# envelope_detection.net
KiCad netlist of a schematic drawn in EAGLE
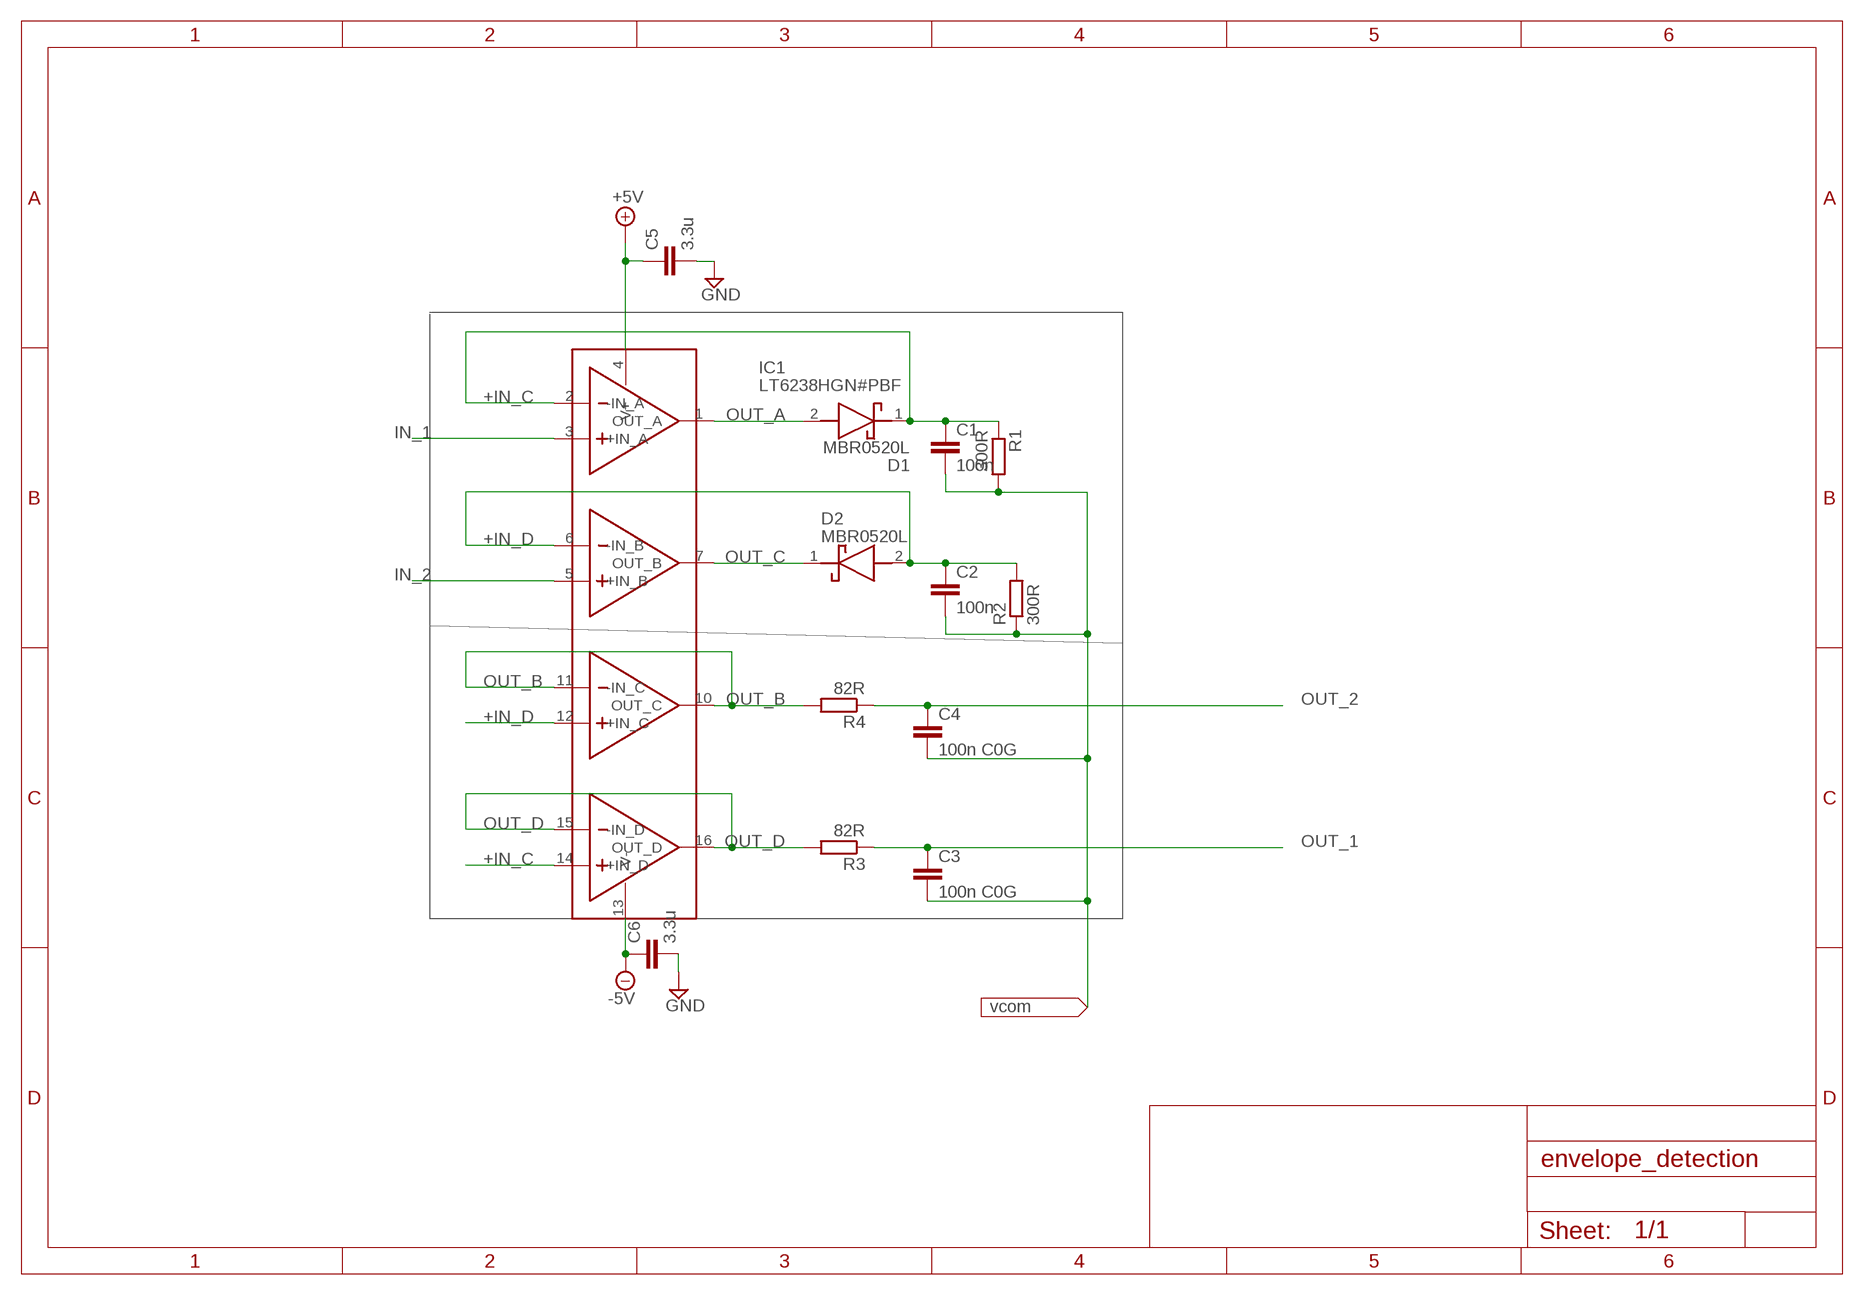
[diagram p0: schematic, sheet 1]

(export (version "E")
  (design (tool "Eeschema 10.0.6"))
  (components
    (comp (ref "C1")
      (value "100n")
      (footprint "eagle-import:C0603")
      (libsource (lib "eagle-import") (part "C-EUC0603"))
    )
    (comp (ref "C2")
      (value "100n")
      (footprint "eagle-import:C0603")
      (libsource (lib "eagle-import") (part "C-EUC0603"))
    )
    (comp (ref "C3")
      (value "100n C0G")
      (footprint "eagle-import:C1206")
      (libsource (lib "eagle-import") (part "C-EUC1206"))
    )
    (comp (ref "C4")
      (value "100n C0G")
      (footprint "eagle-import:C1206")
      (libsource (lib "eagle-import") (part "C-EUC1206"))
    )
    (comp (ref "C5")
      (value "3.3u")
      (footprint "eagle-import:C0402")
      (libsource (lib "eagle-import") (part "C-EUC0402"))
    )
    (comp (ref "C6")
      (value "3.3u")
      (footprint "eagle-import:C0402")
      (libsource (lib "eagle-import") (part "C-EUC0402"))
    )
    (comp (ref "D1")
      (value "MBR0520L")
      (footprint "eagle-import:SOD3816X128N")
      (fields (field (name "MOUSER_PART_NUMBER") "512-MBR0520L") (field (name "RS_PART_NUMBER") "7390521P"))
      (libsource (lib "eagle-import") (part "MBR0520L"))
    )
    (comp (ref "D2")
      (value "MBR0520L")
      (footprint "eagle-import:SOD3816X128N")
      (fields (field (name "MOUSER_PART_NUMBER") "512-MBR0520L") (field (name "RS_PART_NUMBER") "7390521P"))
      (libsource (lib "eagle-import") (part "MBR0520L"))
    )
    (comp (ref "IC1")
      (value "LT6238HGN#PBF")
      (footprint "eagle-import:SOP64P601X175-16N")
      (libsource (lib "eagle-import") (part "LT6238HGN#PBF"))
    )
    (comp (ref "R1")
      (value "300R")
      (footprint "eagle-import:M0805")
      (libsource (lib "eagle-import") (part "R-EU_M0805"))
    )
    (comp (ref "R2")
      (value "300R")
      (footprint "eagle-import:M0805")
      (libsource (lib "eagle-import") (part "R-EU_M0805"))
    )
    (comp (ref "R3")
      (value "82R")
      (footprint "eagle-import:M0805")
      (libsource (lib "eagle-import") (part "R-EU_M0805"))
    )
    (comp (ref "R4")
      (value "82R")
      (footprint "eagle-import:M0805")
      (libsource (lib "eagle-import") (part "R-EU_M0805"))
    )
  )
  (nets
    (net (code "1") (name "+5V") (class "Default")
      (node (ref "C5") (pin "1") (pinfunction "1_1") (pintype "passive"))
      (node (ref "IC1") (pin "4") (pinfunction "V+_4") (pintype "bidirectional"))
    )
    (net (code "2") (name "-5V") (class "Default")
      (node (ref "C6") (pin "1") (pinfunction "1_1") (pintype "passive"))
      (node (ref "IC1") (pin "13") (pinfunction "V-_13") (pintype "bidirectional"))
    )
    (net (code "3") (name "/+IN_C") (class "Default")
      (node (ref "C1") (pin "1") (pinfunction "1_1") (pintype "passive"))
      (node (ref "D1") (pin "1") (pinfunction "K_1") (pintype "bidirectional"))
      (node (ref "IC1") (pin "14") (pinfunction "+IN_D_14") (pintype "bidirectional"))
      (node (ref "IC1") (pin "2") (pinfunction "-IN_A_2") (pintype "bidirectional"))
      (node (ref "R1") (pin "1") (pinfunction "1_1") (pintype "passive"))
    )
    (net (code "4") (name "/+IN_D") (class "Default")
      (node (ref "C2") (pin "1") (pinfunction "1_1") (pintype "passive"))
      (node (ref "D2") (pin "2") (pinfunction "A_2") (pintype "bidirectional"))
      (node (ref "IC1") (pin "12") (pinfunction "+IN_C_12") (pintype "bidirectional"))
      (node (ref "IC1") (pin "6") (pinfunction "-IN_B_6") (pintype "bidirectional"))
      (node (ref "R2") (pin "2") (pinfunction "2_2") (pintype "passive"))
    )
    (net (code "5") (name "/IN_1") (class "Default")
      (node (ref "IC1") (pin "3") (pinfunction "+IN_A_3") (pintype "bidirectional"))
    )
    (net (code "6") (name "/IN_2") (class "Default")
      (node (ref "IC1") (pin "5") (pinfunction "+IN_B_5") (pintype "bidirectional"))
    )
    (net (code "7") (name "/OUT_1") (class "Default")
      (node (ref "C3") (pin "1") (pinfunction "1_1") (pintype "passive"))
      (node (ref "R3") (pin "1") (pinfunction "1_1") (pintype "passive"))
    )
    (net (code "8") (name "/OUT_2") (class "Default")
      (node (ref "C4") (pin "1") (pinfunction "1_1") (pintype "passive"))
      (node (ref "R4") (pin "1") (pinfunction "1_1") (pintype "passive"))
    )
    (net (code "9") (name "/OUT_A") (class "Default")
      (node (ref "D1") (pin "2") (pinfunction "A_2") (pintype "bidirectional"))
      (node (ref "IC1") (pin "1") (pinfunction "OUT_A_1") (pintype "bidirectional"))
    )
    (net (code "10") (name "/OUT_B") (class "Default")
      (node (ref "IC1") (pin "10") (pinfunction "OUT_C_10") (pintype "bidirectional"))
      (node (ref "IC1") (pin "11") (pinfunction "-IN_C_11") (pintype "bidirectional"))
      (node (ref "R4") (pin "2") (pinfunction "2_2") (pintype "passive"))
    )
    (net (code "11") (name "/OUT_C") (class "Default")
      (node (ref "D2") (pin "1") (pinfunction "K_1") (pintype "bidirectional"))
      (node (ref "IC1") (pin "7") (pinfunction "OUT_B_7") (pintype "bidirectional"))
    )
    (net (code "12") (name "/OUT_D") (class "Default")
      (node (ref "IC1") (pin "15") (pinfunction "-IN_D_15") (pintype "bidirectional"))
      (node (ref "IC1") (pin "16") (pinfunction "OUT_D_16") (pintype "bidirectional"))
      (node (ref "R3") (pin "2") (pinfunction "2_2") (pintype "passive"))
    )
    (net (code "13") (name "GND") (class "Default")
      (node (ref "C5") (pin "2") (pinfunction "2_2") (pintype "passive"))
      (node (ref "C6") (pin "2") (pinfunction "2_2") (pintype "passive"))
    )
    (net (code "14") (name "Net-(C1-Pad2)") (class "Default")
      (node (ref "C1") (pin "2") (pinfunction "2_2") (pintype "passive"))
      (node (ref "C2") (pin "2") (pinfunction "2_2") (pintype "passive"))
      (node (ref "C3") (pin "2") (pinfunction "2_2") (pintype "passive"))
      (node (ref "C4") (pin "2") (pinfunction "2_2") (pintype "passive"))
      (node (ref "R1") (pin "2") (pinfunction "2_2") (pintype "passive"))
      (node (ref "R2") (pin "1") (pinfunction "1_1") (pintype "passive"))
    )
  )
)
